# Power_PCB.net
KiCad netlist of a schematic drawn in EAGLE
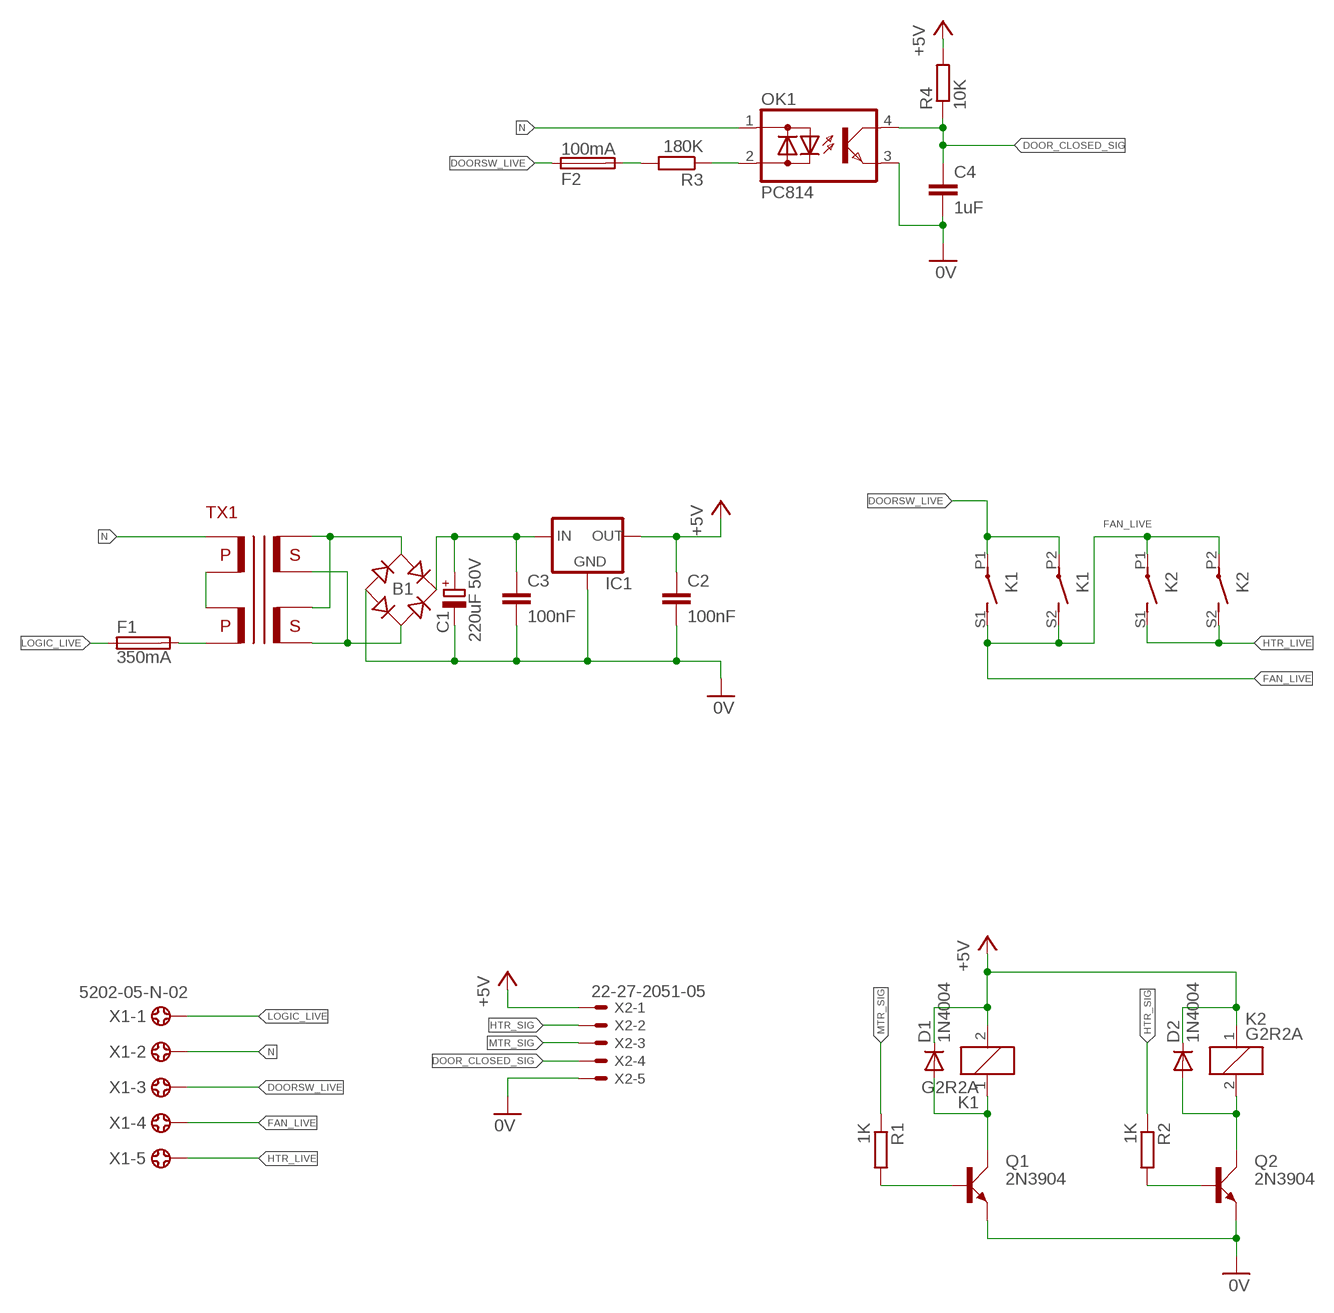
[diagram p0: schematic, sheet 1]

(export (version "E")
  (design (tool "Eeschema 10.0.6"))
  (components
    (comp (ref "B1")
      (value "RECTIFIER-RB1A")
      (footprint "eagle-import:RB1A")
      (libsource (lib "eagle-import") (part "RECTIFIER-RB1A"))
    )
    (comp (ref "C1")
      (value "220uF 50V")
      (footprint "eagle-import:E3,5-8")
      (libsource (lib "eagle-import") (part "CPOL-EUE3.5-8"))
    )
    (comp (ref "C2")
      (value "100nF")
      (footprint "eagle-import:C025-025X050")
      (libsource (lib "eagle-import") (part "C-EU025-025X050"))
    )
    (comp (ref "C3")
      (value "100nF")
      (footprint "eagle-import:C025-025X050")
      (libsource (lib "eagle-import") (part "C-EU025-025X050"))
    )
    (comp (ref "C4")
      (value "1uF")
      (footprint "eagle-import:C025-025X050")
      (libsource (lib "eagle-import") (part "C-EU025-025X050"))
    )
    (comp (ref "D1")
      (value "1N4004")
      (footprint "eagle-import:DO41-10")
      (libsource (lib "eagle-import") (part "1N4004"))
    )
    (comp (ref "D2")
      (value "1N4004")
      (footprint "eagle-import:DO41-10")
      (libsource (lib "eagle-import") (part "1N4004"))
    )
    (comp (ref "F1")
      (value "350mA")
      (footprint "eagle-import:SH25")
      (fields (field (name "MF") "SCHURTER") (field (name "MPN") "0031.8211"))
      (libsource (lib "eagle-import") (part "SH25"))
    )
    (comp (ref "F2")
      (value "100mA")
      (footprint "eagle-import:SH25")
      (fields (field (name "MF") "SCHURTER") (field (name "MPN") "0031.8211"))
      (libsource (lib "eagle-import") (part "SH25"))
    )
    (comp (ref "IC1")
      (value "V_REG_78XX-TO-220")
      (footprint "eagle-import:TO-220-ALT")
      (libsource (lib "eagle-import") (part "V_REG_78XX-TO-220"))
    )
    (comp (ref "K1")
      (value "G2R2A")
      (footprint "eagle-import:G2R2A")
      (fields (field (name "MPN") "G2R-2A-DC24"))
      (libsource (lib "eagle-import") (part "G2R2A"))
    )
    (comp (ref "K2")
      (value "G2R2A")
      (footprint "eagle-import:G2R2A")
      (fields (field (name "MPN") "G2R-2A-DC24"))
      (libsource (lib "eagle-import") (part "G2R2A"))
    )
    (comp (ref "OK1")
      (value "PC814")
      (footprint "eagle-import:DIL04")
      (libsource (lib "eagle-import") (part "PC814"))
    )
    (comp (ref "Q1")
      (value "2N3904")
      (footprint "eagle-import:TO92D")
      (libsource (lib "eagle-import") (part "2N3904"))
    )
    (comp (ref "Q2")
      (value "2N3904")
      (footprint "eagle-import:TO92D")
      (libsource (lib "eagle-import") (part "2N3904"))
    )
    (comp (ref "R1")
      (value "1K")
      (footprint "eagle-import:0207_10")
      (libsource (lib "eagle-import") (part "R-EU_0207/10"))
    )
    (comp (ref "R2")
      (value "1K")
      (footprint "eagle-import:0207_10")
      (libsource (lib "eagle-import") (part "R-EU_0207/10"))
    )
    (comp (ref "R3")
      (value "180K")
      (footprint "eagle-import:P0613V")
      (libsource (lib "eagle-import") (part "R-EU_0613/5V"))
    )
    (comp (ref "R4")
      (value "10K")
      (footprint "eagle-import:0207_10")
      (libsource (lib "eagle-import") (part "R-EU_0207/10"))
    )
    (comp (ref "TX1")
      (value "RS504-397")
      (footprint "eagle-import:RS504-397")
      (libsource (lib "eagle-import") (part "RS504-397"))
    )
    (comp (ref "X1")
      (value "5202-05-N-02")
      (footprint "eagle-import:5202-05-N-02")
      (libsource (lib "eagle-import") (part "5202-05-N-02"))
    )
    (comp (ref "X2")
      (value "22-27-2051-05")
      (footprint "eagle-import:6410-05")
      (libsource (lib "eagle-import") (part "22-?-0527-2051"))
    )
  )
  (nets
    (net (code "1") (name "+5V") (class "Default")
      (node (ref "C2") (pin "1") (pinfunction "1_1") (pintype "passive"))
      (node (ref "D1") (pin "C") (pinfunction "C_C") (pintype "passive"))
      (node (ref "D2") (pin "C") (pinfunction "C_C") (pintype "passive"))
      (node (ref "IC1") (pin "OUT") (pinfunction "OUT_OUT") (pintype "output"))
      (node (ref "K1") (pin "2") (pinfunction "2_2") (pintype "passive"))
      (node (ref "K2") (pin "1") (pinfunction "1_1") (pintype "passive"))
      (node (ref "R4") (pin "2") (pinfunction "2_2") (pintype "passive"))
      (node (ref "X2") (pin "1") (pinfunction "S_1") (pintype "passive"))
    )
    (net (code "2") (name "0V") (class "Default")
      (node (ref "B1") (pin "-") (pinfunction "-_-") (pintype "passive"))
      (node (ref "C1") (pin "-") (pinfunction "-_-") (pintype "passive"))
      (node (ref "C2") (pin "2") (pinfunction "2_2") (pintype "passive"))
      (node (ref "C3") (pin "2") (pinfunction "2_2") (pintype "passive"))
      (node (ref "C4") (pin "2") (pinfunction "2_2") (pintype "passive"))
      (node (ref "IC1") (pin "GND") (pinfunction "GND_GND") (pintype "input"))
      (node (ref "OK1") (pin "3") (pinfunction "E_3") (pintype "passive"))
      (node (ref "Q1") (pin "E") (pinfunction "E_E") (pintype "passive"))
      (node (ref "Q2") (pin "E") (pinfunction "E_E") (pintype "passive"))
      (node (ref "X2") (pin "5") (pinfunction "S_5") (pintype "passive"))
    )
    (net (code "3") (name "DOORSW_LIVE") (class "Default")
      (node (ref "F2") (pin "1") (pinfunction "1_1") (pintype "passive"))
      (node (ref "K1") (pin "P1") (pinfunction "P_P1") (pintype "passive"))
      (node (ref "K1") (pin "P2") (pinfunction "P_P2") (pintype "passive"))
      (node (ref "X1") (pin "3") (pinfunction "1_3") (pintype "passive"))
    )
    (net (code "4") (name "DOOR_CLOSED_SIG") (class "Default")
      (node (ref "C4") (pin "1") (pinfunction "1_1") (pintype "passive"))
      (node (ref "OK1") (pin "4") (pinfunction "C_4") (pintype "passive"))
      (node (ref "R4") (pin "1") (pinfunction "1_1") (pintype "passive"))
      (node (ref "X2") (pin "4") (pinfunction "S_4") (pintype "passive"))
    )
    (net (code "5") (name "FAN_LIVE") (class "Default")
      (node (ref "K1") (pin "S1") (pinfunction "S_S1") (pintype "passive"))
      (node (ref "K1") (pin "S2") (pinfunction "S_S2") (pintype "passive"))
      (node (ref "K2") (pin "P1") (pinfunction "P_P1") (pintype "passive"))
      (node (ref "K2") (pin "P2") (pinfunction "P_P2") (pintype "passive"))
      (node (ref "X1") (pin "4") (pinfunction "1_4") (pintype "passive"))
    )
    (net (code "6") (name "HTR_LIVE") (class "Default")
      (node (ref "K2") (pin "S1") (pinfunction "S_S1") (pintype "passive"))
      (node (ref "K2") (pin "S2") (pinfunction "S_S2") (pintype "passive"))
      (node (ref "X1") (pin "5") (pinfunction "1_5") (pintype "passive"))
    )
    (net (code "7") (name "HTR_SIG") (class "Default")
      (node (ref "R2") (pin "1") (pinfunction "1_1") (pintype "passive"))
      (node (ref "X2") (pin "2") (pinfunction "S_2") (pintype "passive"))
    )
    (net (code "8") (name "LOGIC_LIVE") (class "Default")
      (node (ref "F1") (pin "1") (pinfunction "1_1") (pintype "passive"))
      (node (ref "X1") (pin "1") (pinfunction "1_1") (pintype "passive"))
    )
    (net (code "9") (name "MTR_SIG") (class "Default")
      (node (ref "R1") (pin "1") (pinfunction "1_1") (pintype "passive"))
      (node (ref "X2") (pin "3") (pinfunction "S_3") (pintype "passive"))
    )
    (net (code "10") (name "N") (class "Default")
      (node (ref "OK1") (pin "1") (pinfunction "AC1_1") (pintype "passive"))
      (node (ref "TX1") (pin "115V1") (pinfunction "115V1_115V1") (pintype "bidirectional"))
      (node (ref "X1") (pin "2") (pinfunction "1_2") (pintype "passive"))
    )
    (net (code "11") (name "Net-(B1-Pad+)") (class "Default")
      (node (ref "B1") (pin "+") (pinfunction "+_+") (pintype "passive"))
      (node (ref "C1") (pin "+") (pinfunction "+_+") (pintype "passive"))
      (node (ref "C3") (pin "1") (pinfunction "1_1") (pintype "passive"))
      (node (ref "IC1") (pin "IN") (pinfunction "IN_IN") (pintype "input"))
    )
    (net (code "12") (name "Net-(B1-PadAC1)") (class "Default")
      (node (ref "B1") (pin "AC1") (pinfunction "AC1_AC1") (pintype "passive"))
      (node (ref "TX1") (pin "12V1") (pinfunction "12V1_12V1") (pintype "bidirectional"))
      (node (ref "TX1") (pin "12V2") (pinfunction "12V2_12V2") (pintype "bidirectional"))
    )
    (net (code "13") (name "Net-(B1-PadAC2)") (class "Default")
      (node (ref "B1") (pin "AC2") (pinfunction "AC2_AC2") (pintype "passive"))
      (node (ref "TX1") (pin "12V1_0") (pinfunction "12V1_0_12V1_0") (pintype "bidirectional"))
      (node (ref "TX1") (pin "12V2_0") (pinfunction "12V2_0_12V2_0") (pintype "bidirectional"))
    )
    (net (code "14") (name "Net-(D1-PadA)") (class "Default")
      (node (ref "D1") (pin "A") (pinfunction "A_A") (pintype "passive"))
      (node (ref "K1") (pin "1") (pinfunction "1_1") (pintype "passive"))
      (node (ref "Q1") (pin "C") (pinfunction "C_C") (pintype "passive"))
    )
    (net (code "15") (name "Net-(D2-PadA)") (class "Default")
      (node (ref "D2") (pin "A") (pinfunction "A_A") (pintype "passive"))
      (node (ref "K2") (pin "2") (pinfunction "2_2") (pintype "passive"))
      (node (ref "Q2") (pin "C") (pinfunction "C_C") (pintype "passive"))
    )
    (net (code "16") (name "Net-(F1-Pad2)") (class "Default")
      (node (ref "F1") (pin "2") (pinfunction "2_2") (pintype "passive"))
      (node (ref "TX1") (pin "0V2") (pinfunction "0V2_0V2") (pintype "bidirectional"))
    )
    (net (code "17") (name "Net-(F2-Pad2)") (class "Default")
      (node (ref "F2") (pin "2") (pinfunction "2_2") (pintype "passive"))
      (node (ref "R3") (pin "2") (pinfunction "2_2") (pintype "passive"))
    )
    (net (code "18") (name "Net-(OK1-AC2)") (class "Default")
      (node (ref "OK1") (pin "2") (pinfunction "AC2_2") (pintype "passive"))
      (node (ref "R3") (pin "1") (pinfunction "1_1") (pintype "passive"))
    )
    (net (code "19") (name "Net-(Q1-PadB)") (class "Default")
      (node (ref "Q1") (pin "B") (pinfunction "B_B") (pintype "passive"))
      (node (ref "R1") (pin "2") (pinfunction "2_2") (pintype "passive"))
    )
    (net (code "20") (name "Net-(Q2-PadB)") (class "Default")
      (node (ref "Q2") (pin "B") (pinfunction "B_B") (pintype "passive"))
      (node (ref "R2") (pin "2") (pinfunction "2_2") (pintype "passive"))
    )
    (net (code "21") (name "Net-(TX1-Pad0V1)") (class "Default")
      (node (ref "TX1") (pin "0V1") (pinfunction "0V1_0V1") (pintype "bidirectional"))
      (node (ref "TX1") (pin "115V2") (pinfunction "115V2_115V2") (pintype "bidirectional"))
    )
  )
)
